# HPLEDShield-v2_5.net
KiCad netlist of a schematic drawn in EAGLE
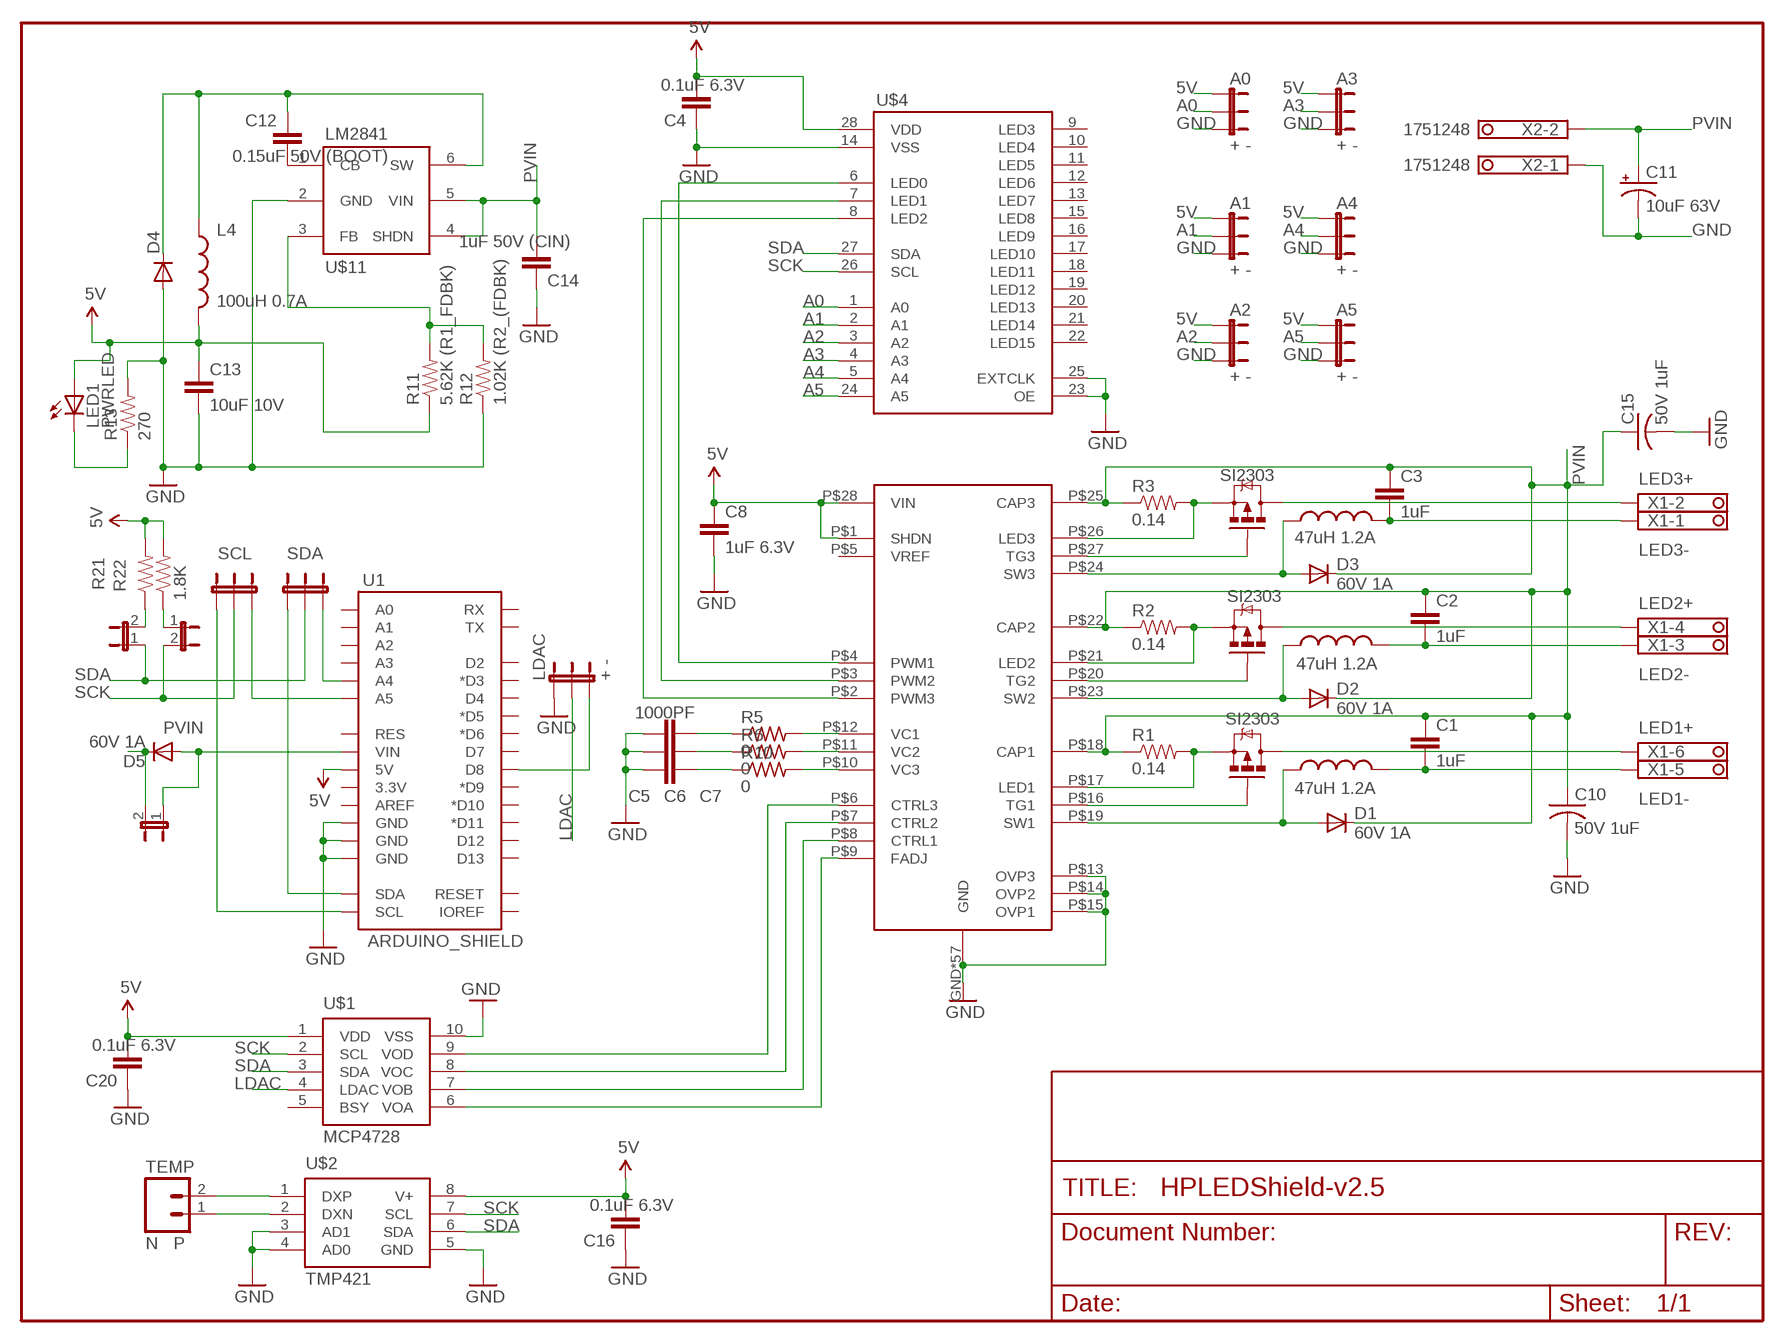
[diagram p0: schematic, sheet 1]

(export (version "E")
  (design (tool "Eeschema 10.0.6"))
  (components
    (comp (ref "A0")
      (value "+ -")
      (footprint "eagle-import:SJ_3")
      (libsource (lib "eagle-import") (part "JUMPER-3SMD"))
    )
    (comp (ref "A1")
      (value "+ -")
      (footprint "eagle-import:SJ_3")
      (libsource (lib "eagle-import") (part "JUMPER-3SMD"))
    )
    (comp (ref "A2")
      (value "+ -")
      (footprint "eagle-import:SJ_3")
      (libsource (lib "eagle-import") (part "JUMPER-3SMD"))
    )
    (comp (ref "A3")
      (value "+ -")
      (footprint "eagle-import:SJ_3")
      (libsource (lib "eagle-import") (part "JUMPER-3SMD"))
    )
    (comp (ref "A4")
      (value "+ -")
      (footprint "eagle-import:SJ_3")
      (libsource (lib "eagle-import") (part "JUMPER-3SMD"))
    )
    (comp (ref "A5")
      (value "+ -")
      (footprint "eagle-import:SJ_3")
      (libsource (lib "eagle-import") (part "JUMPER-3SMD"))
    )
    (comp (ref "C1")
      (value "1uF")
      (footprint "eagle-import:0805")
      (libsource (lib "eagle-import") (part "CAP0805"))
    )
    (comp (ref "C2")
      (value "1uF")
      (footprint "eagle-import:0805")
      (libsource (lib "eagle-import") (part "CAP0805"))
    )
    (comp (ref "C3")
      (value "1uF")
      (footprint "eagle-import:0805")
      (libsource (lib "eagle-import") (part "CAP0805"))
    )
    (comp (ref "C4")
      (value "0.1uF 6.3V")
      (footprint "eagle-import:0402-CAP")
      (libsource (lib "eagle-import") (part "CAP0402-CAP"))
    )
    (comp (ref "C5")
      (value "1000PF")
      (footprint "eagle-import:0402-CAP")
      (libsource (lib "eagle-import") (part "CAP0402-CAP"))
    )
    (comp (ref "C6")
      (value "1000PF")
      (footprint "eagle-import:0402-CAP")
      (libsource (lib "eagle-import") (part "CAP0402-CAP"))
    )
    (comp (ref "C7")
      (value "1000PF")
      (footprint "eagle-import:0402-CAP")
      (libsource (lib "eagle-import") (part "CAP0402-CAP"))
    )
    (comp (ref "C8")
      (value "1uF 6.3V")
      (footprint "eagle-import:0402-CAP")
      (libsource (lib "eagle-import") (part "CAP0402-CAP"))
    )
    (comp (ref "C10")
      (value "50V 1uF")
      (footprint "eagle-import:C1210")
      (libsource (lib "eagle-import") (part "C-USC1210"))
    )
    (comp (ref "C11")
      (value "10uF 63V")
      (footprint "eagle-import:PANASONIC_D")
      (libsource (lib "eagle-import") (part "CAP_POLD"))
    )
    (comp (ref "C12")
      (value "0.15uF 50V (BOOT)")
      (footprint "eagle-import:0603-CAP")
      (libsource (lib "eagle-import") (part "CAP0603-CAP"))
    )
    (comp (ref "C13")
      (value "10uF 10V")
      (footprint "eagle-import:0805")
      (libsource (lib "eagle-import") (part "CAP0805"))
    )
    (comp (ref "C14")
      (value "1uF 50V (CIN)")
      (footprint "eagle-import:1206")
      (libsource (lib "eagle-import") (part "CAP1206"))
    )
    (comp (ref "C15")
      (value "50V 1uF")
      (footprint "eagle-import:C1210")
      (libsource (lib "eagle-import") (part "C-USC1210"))
    )
    (comp (ref "C16")
      (value "0.1uF 6.3V")
      (footprint "eagle-import:0402-CAP")
      (libsource (lib "eagle-import") (part "CAP0402-CAP"))
    )
    (comp (ref "C20")
      (value "0.1uF 6.3V")
      (footprint "eagle-import:0402-CAP")
      (libsource (lib "eagle-import") (part "CAP0402-CAP"))
    )
    (comp (ref "D1")
      (value "60V 1A")
      (footprint "eagle-import:SOD123")
      (libsource (lib "eagle-import") (part "DIODES0D123"))
    )
    (comp (ref "D2")
      (value "60V 1A")
      (footprint "eagle-import:SOD123")
      (libsource (lib "eagle-import") (part "DIODES0D123"))
    )
    (comp (ref "D3")
      (value "60V 1A")
      (footprint "eagle-import:SOD123")
      (libsource (lib "eagle-import") (part "DIODES0D123"))
    )
    (comp (ref "D4")
      (value "DIODE-SCHOTTKY_ 60V 1A")
      (footprint "eagle-import:SOD123")
      (libsource (lib "eagle-import") (part "DIODES0D123"))
    )
    (comp (ref "D5")
      (value "60V 1A")
      (footprint "eagle-import:SOD123")
      (libsource (lib "eagle-import") (part "DIODES0D123"))
    )
    (comp (ref "JP1")
      (value "PWM3")
      (footprint "eagle-import:SJ_2S-NO")
      (libsource (lib "eagle-import") (part "JUMPER-2SMD-NO"))
    )
    (comp (ref "JP2")
      (value "PWM3")
      (footprint "eagle-import:SJ_2S")
      (libsource (lib "eagle-import") (part "JUMPER-2SMD-NC"))
    )
    (comp (ref "JP3")
      (value "PWM3")
      (footprint "eagle-import:SJ_2S")
      (libsource (lib "eagle-import") (part "JUMPER-2SMD-NC"))
    )
    (comp (ref "L1")
      (value "47uH 1.2A")
      (footprint "eagle-import:ELL8TP")
      (libsource (lib "eagle-import") (part "INDUCTORELL8"))
    )
    (comp (ref "L2")
      (value "47uH 1.2A")
      (footprint "eagle-import:ELL8TP")
      (libsource (lib "eagle-import") (part "INDUCTORELL8"))
    )
    (comp (ref "L3")
      (value "47uH 1.2A")
      (footprint "eagle-import:ELL8TP")
      (libsource (lib "eagle-import") (part "INDUCTORELL8"))
    )
    (comp (ref "L4")
      (value "100uH 0.7A")
      (footprint "eagle-import:ELL6UH")
      (libsource (lib "eagle-import") (part "INDUCTOR6UH"))
    )
    (comp (ref "LDAC")
      (value "+ -")
      (footprint "eagle-import:SJ_3")
      (libsource (lib "eagle-import") (part "JUMPER-3SMD"))
    )
    (comp (ref "LED1")
      (value "PWRLED")
      (footprint "eagle-import:LED-0603")
      (libsource (lib "eagle-import") (part "LED0603"))
    )
    (comp (ref "LT3496")
      (value "LT3496")
      (footprint "eagle-import:LT3694_TSSOP")
      (libsource (lib "eagle-import") (part "LT3496"))
    )
    (comp (ref "Q1")
      (value "SI2303")
      (footprint "eagle-import:SOT-23")
      (libsource (lib "eagle-import") (part "SI2303"))
    )
    (comp (ref "Q2")
      (value "SI2303")
      (footprint "eagle-import:SOT-23")
      (libsource (lib "eagle-import") (part "SI2303"))
    )
    (comp (ref "Q3")
      (value "SI2303")
      (footprint "eagle-import:SOT-23")
      (libsource (lib "eagle-import") (part "SI2303"))
    )
    (comp (ref "R1")
      (value "0.14")
      (footprint "eagle-import:0603-RES")
      (libsource (lib "eagle-import") (part "RESISTOR0603-RES"))
    )
    (comp (ref "R2")
      (value "0.14")
      (footprint "eagle-import:0603-RES")
      (libsource (lib "eagle-import") (part "RESISTOR0603-RES"))
    )
    (comp (ref "R3")
      (value "0.14")
      (footprint "eagle-import:0603-RES")
      (libsource (lib "eagle-import") (part "RESISTOR0603-RES"))
    )
    (comp (ref "R5")
      (value "0")
      (footprint "eagle-import:R0402")
      (libsource (lib "eagle-import") (part "R-US_R0402"))
    )
    (comp (ref "R6")
      (value "0")
      (footprint "eagle-import:R0402")
      (libsource (lib "eagle-import") (part "R-US_R0402"))
    )
    (comp (ref "R10")
      (value "0")
      (footprint "eagle-import:R0402")
      (libsource (lib "eagle-import") (part "R-US_R0402"))
    )
    (comp (ref "R11")
      (value "5.62K (R1_FDBK)")
      (footprint "eagle-import:0603-RES")
      (libsource (lib "eagle-import") (part "RESISTOR0603-RES"))
    )
    (comp (ref "R12")
      (value "1.02K (R2_(FDBK)")
      (footprint "eagle-import:0603-RES")
      (libsource (lib "eagle-import") (part "RESISTOR0603-RES"))
    )
    (comp (ref "R13")
      (value "270")
      (footprint "eagle-import:0603-RES")
      (libsource (lib "eagle-import") (part "RESISTOR0603-RES"))
    )
    (comp (ref "R21")
      (value "1.8K")
      (footprint "eagle-import:0402-RES")
      (libsource (lib "eagle-import") (part "RESISTOR0402-RES"))
    )
    (comp (ref "R22")
      (value "1.8K")
      (footprint "eagle-import:0402-RES")
      (libsource (lib "eagle-import") (part "RESISTOR0402-RES"))
    )
    (comp (ref "SCL")
      (value "JUMPER-3SMD")
      (footprint "eagle-import:SJ_3")
      (libsource (lib "eagle-import") (part "JUMPER-3SMD"))
    )
    (comp (ref "SDA")
      (value "JUMPER-3SMD")
      (footprint "eagle-import:SJ_3")
      (libsource (lib "eagle-import") (part "JUMPER-3SMD"))
    )
    (comp (ref "TEMP")
      (value "N P")
      (footprint "eagle-import:1X02")
      (libsource (lib "eagle-import") (part "M02PTH"))
    )
    (comp (ref "U$1")
      (value "MCP4728")
      (footprint "eagle-import:MSOP10")
      (libsource (lib "eagle-import") (part "MCP4728"))
    )
    (comp (ref "U$2")
      (value "TMP421")
      (footprint "eagle-import:SOT23-8")
      (libsource (lib "eagle-import") (part "TMP421"))
    )
    (comp (ref "U$4")
      (value "PCA9685")
      (footprint "eagle-import:TSSOP28")
      (libsource (lib "eagle-import") (part "PCA9685"))
    )
    (comp (ref "U$11")
      (value "LM2841")
      (footprint "eagle-import:TSOT-6")
      (libsource (lib "eagle-import") (part "LM2841"))
    )
    (comp (ref "U1")
      (value "ARDUINO_SHIELD")
      (footprint "eagle-import:DUEMILANOVE_VIAS")
      (libsource (lib "eagle-import") (part "ARDUINO_SHIELDNO_SILK"))
    )
    (comp (ref "X1")
      (value "LED1+")
      (footprint "eagle-import:1751280")
      (fields (field (name "MPN") "1751280"))
      (libsource (lib "eagle-import") (part "1751280"))
    )
    (comp (ref "X2")
      (value "1751248")
      (footprint "eagle-import:1751248")
      (libsource (lib "eagle-import") (part "1751248"))
    )
  )
  (nets
    (net (code "1") (name "/A0") (class "Default")
      (node (ref "A0") (pin "2") (pinfunction "2_2") (pintype "passive"))
      (node (ref "U$4") (pin "1") (pinfunction "A0_1") (pintype "bidirectional"))
    )
    (net (code "2") (name "/A1") (class "Default")
      (node (ref "A1") (pin "2") (pinfunction "2_2") (pintype "passive"))
      (node (ref "U$4") (pin "2") (pinfunction "A1_2") (pintype "bidirectional"))
    )
    (net (code "3") (name "/A2") (class "Default")
      (node (ref "A2") (pin "2") (pinfunction "2_2") (pintype "passive"))
      (node (ref "U$4") (pin "3") (pinfunction "A2_3") (pintype "bidirectional"))
    )
    (net (code "4") (name "/A3") (class "Default")
      (node (ref "A3") (pin "2") (pinfunction "2_2") (pintype "passive"))
      (node (ref "U$4") (pin "4") (pinfunction "A3_4") (pintype "bidirectional"))
    )
    (net (code "5") (name "/A4") (class "Default")
      (node (ref "A4") (pin "2") (pinfunction "2_2") (pintype "passive"))
      (node (ref "U$4") (pin "5") (pinfunction "A4_5") (pintype "bidirectional"))
    )
    (net (code "6") (name "/A5") (class "Default")
      (node (ref "A5") (pin "2") (pinfunction "2_2") (pintype "passive"))
      (node (ref "U$4") (pin "24") (pinfunction "A5_24") (pintype "bidirectional"))
    )
    (net (code "7") (name "/LDAC") (class "Default")
      (node (ref "LDAC") (pin "2") (pinfunction "2_2") (pintype "passive"))
      (node (ref "U$1") (pin "4") (pinfunction "LDAC_4") (pintype "bidirectional"))
    )
    (net (code "8") (name "/PVIN") (class "Default")
      (node (ref "C1") (pin "1") (pinfunction "1_1") (pintype "passive"))
      (node (ref "C10") (pin "1") (pinfunction "1_1") (pintype "passive"))
      (node (ref "C11") (pin "+") (pinfunction "+_+") (pintype "passive"))
      (node (ref "C14") (pin "2") (pinfunction "2_2") (pintype "passive"))
      (node (ref "C15") (pin "1") (pinfunction "1_1") (pintype "passive"))
      (node (ref "C2") (pin "1") (pinfunction "1_1") (pintype "passive"))
      (node (ref "C3") (pin "1") (pinfunction "1_1") (pintype "passive"))
      (node (ref "D1") (pin "1") (pinfunction "C_1") (pintype "passive"))
      (node (ref "D2") (pin "1") (pinfunction "C_1") (pintype "passive"))
      (node (ref "D3") (pin "1") (pinfunction "C_1") (pintype "passive"))
      (node (ref "D5") (pin "1") (pinfunction "C_1") (pintype "passive"))
      (node (ref "JP1") (pin "2") (pinfunction "2_2") (pintype "passive"))
      (node (ref "LT3496") (pin "P$18") (pinfunction "CAP1_P$18") (pintype "bidirectional"))
      (node (ref "LT3496") (pin "P$22") (pinfunction "CAP2_P$22") (pintype "bidirectional"))
      (node (ref "LT3496") (pin "P$25") (pinfunction "CAP3_P$25") (pintype "bidirectional"))
      (node (ref "R1") (pin "1") (pinfunction "1_1") (pintype "passive"))
      (node (ref "R2") (pin "1") (pinfunction "1_1") (pintype "passive"))
      (node (ref "R3") (pin "1") (pinfunction "1_1") (pintype "passive"))
      (node (ref "U$11") (pin "4") (pinfunction "SHDN_4") (pintype "bidirectional"))
      (node (ref "U$11") (pin "5") (pinfunction "VIN_5") (pintype "bidirectional"))
      (node (ref "X2") (pin "2") (pinfunction "K_2") (pintype "passive"))
    )
    (net (code "9") (name "/SCK") (class "Default")
      (node (ref "JP3") (pin "2") (pinfunction "2_2") (pintype "passive"))
      (node (ref "SCL") (pin "2") (pinfunction "2_2") (pintype "passive"))
      (node (ref "U$1") (pin "2") (pinfunction "SCL_2") (pintype "bidirectional"))
      (node (ref "U$2") (pin "7") (pinfunction "SCL_7") (pintype "bidirectional"))
      (node (ref "U$4") (pin "26") (pinfunction "SCL_26") (pintype "bidirectional"))
    )
    (net (code "10") (name "/SDA") (class "Default")
      (node (ref "JP2") (pin "1") (pinfunction "1_1") (pintype "passive"))
      (node (ref "SDA") (pin "2") (pinfunction "2_2") (pintype "passive"))
      (node (ref "U$1") (pin "3") (pinfunction "SDA_3") (pintype "bidirectional"))
      (node (ref "U$2") (pin "6") (pinfunction "SDA_6") (pintype "bidirectional"))
      (node (ref "U$4") (pin "27") (pinfunction "SDA_27") (pintype "bidirectional"))
    )
    (net (code "11") (name "5V") (class "Default")
      (node (ref "A0") (pin "1") (pinfunction "1_1") (pintype "passive"))
      (node (ref "A1") (pin "1") (pinfunction "1_1") (pintype "passive"))
      (node (ref "A2") (pin "1") (pinfunction "1_1") (pintype "passive"))
      (node (ref "A3") (pin "1") (pinfunction "1_1") (pintype "passive"))
      (node (ref "A4") (pin "1") (pinfunction "1_1") (pintype "passive"))
      (node (ref "A5") (pin "1") (pinfunction "1_1") (pintype "passive"))
      (node (ref "C13") (pin "1") (pinfunction "1_1") (pintype "passive"))
      (node (ref "C16") (pin "2") (pinfunction "2_2") (pintype "passive"))
      (node (ref "C20") (pin "2") (pinfunction "2_2") (pintype "passive"))
      (node (ref "C4") (pin "2") (pinfunction "2_2") (pintype "passive"))
      (node (ref "C8") (pin "1") (pinfunction "1_1") (pintype "passive"))
      (node (ref "L4") (pin "P$2") (pinfunction "2_P$2") (pintype "passive"))
      (node (ref "LED1") (pin "A") (pinfunction "A_A") (pintype "passive"))
      (node (ref "LT3496") (pin "P$1") (pinfunction "SHDN_P$1") (pintype "bidirectional"))
      (node (ref "LT3496") (pin "P$28") (pinfunction "VIN_P$28") (pintype "power_in"))
      (node (ref "R11") (pin "1") (pinfunction "1_1") (pintype "passive"))
      (node (ref "R21") (pin "2") (pinfunction "2_2") (pintype "passive"))
      (node (ref "R22") (pin "2") (pinfunction "2_2") (pintype "passive"))
      (node (ref "U$1") (pin "1") (pinfunction "VDD_1") (pintype "bidirectional"))
      (node (ref "U$2") (pin "8") (pinfunction "V+_8") (pintype "bidirectional"))
      (node (ref "U$4") (pin "28") (pinfunction "VDD_28") (pintype "bidirectional"))
      (node (ref "U1") (pin "5V") (pinfunction "5V_5V") (pintype "bidirectional"))
    )
    (net (code "12") (name "GND") (class "Default")
      (node (ref "A0") (pin "3") (pinfunction "3_3") (pintype "passive"))
      (node (ref "A1") (pin "3") (pinfunction "3_3") (pintype "passive"))
      (node (ref "A2") (pin "3") (pinfunction "3_3") (pintype "passive"))
      (node (ref "A3") (pin "3") (pinfunction "3_3") (pintype "passive"))
      (node (ref "A4") (pin "3") (pinfunction "3_3") (pintype "passive"))
      (node (ref "A5") (pin "3") (pinfunction "3_3") (pintype "passive"))
      (node (ref "C10") (pin "2") (pinfunction "2_2") (pintype "passive"))
      (node (ref "C11") (pin "-") (pinfunction "-_-") (pintype "passive"))
      (node (ref "C13") (pin "2") (pinfunction "2_2") (pintype "passive"))
      (node (ref "C14") (pin "1") (pinfunction "1_1") (pintype "passive"))
      (node (ref "C15") (pin "2") (pinfunction "2_2") (pintype "passive"))
      (node (ref "C16") (pin "1") (pinfunction "1_1") (pintype "passive"))
      (node (ref "C20") (pin "1") (pinfunction "1_1") (pintype "passive"))
      (node (ref "C4") (pin "1") (pinfunction "1_1") (pintype "passive"))
      (node (ref "C5") (pin "1") (pinfunction "1_1") (pintype "passive"))
      (node (ref "C6") (pin "1") (pinfunction "1_1") (pintype "passive"))
      (node (ref "C7") (pin "1") (pinfunction "1_1") (pintype "passive"))
      (node (ref "C8") (pin "2") (pinfunction "2_2") (pintype "passive"))
      (node (ref "D4") (pin "2") (pinfunction "A_2") (pintype "passive"))
      (node (ref "LDAC") (pin "1") (pinfunction "1_1") (pintype "passive"))
      (node (ref "LT3496") (pin "GND") (pinfunction "GND_GND") (pintype "bidirectional"))
      (node (ref "LT3496") (pin "P$13") (pinfunction "OVP3_P$13") (pintype "bidirectional"))
      (node (ref "LT3496") (pin "P$14") (pinfunction "OVP2_P$14") (pintype "bidirectional"))
      (node (ref "LT3496") (pin "P$15") (pinfunction "OVP1_P$15") (pintype "bidirectional"))
      (node (ref "LT3496") (pin "P$29") (pinfunction "GND_P$29") (pintype "bidirectional"))
      (node (ref "LT3496") (pin "P$30") (pinfunction "GND_P$30") (pintype "bidirectional"))
      (node (ref "LT3496") (pin "P$31") (pinfunction "GND_P$31") (pintype "bidirectional"))
      (node (ref "LT3496") (pin "P$32") (pinfunction "GND_P$32") (pintype "bidirectional"))
      (node (ref "LT3496") (pin "P$33") (pinfunction "GND_P$33") (pintype "bidirectional"))
      (node (ref "LT3496") (pin "P$34") (pinfunction "GND_P$34") (pintype "bidirectional"))
      (node (ref "LT3496") (pin "P$35") (pinfunction "GND_P$35") (pintype "bidirectional"))
      (node (ref "LT3496") (pin "P$36") (pinfunction "GND_P$36") (pintype "bidirectional"))
      (node (ref "LT3496") (pin "P$37") (pinfunction "GND_P$37") (pintype "bidirectional"))
      (node (ref "LT3496") (pin "P$38") (pinfunction "GND_P$38") (pintype "bidirectional"))
      (node (ref "LT3496") (pin "P$39") (pinfunction "GND_P$39") (pintype "bidirectional"))
      (node (ref "LT3496") (pin "P$40") (pinfunction "GND_P$40") (pintype "bidirectional"))
      (node (ref "LT3496") (pin "P$41") (pinfunction "GND_P$41") (pintype "bidirectional"))
      (node (ref "LT3496") (pin "P$42") (pinfunction "GND_P$42") (pintype "bidirectional"))
      (node (ref "LT3496") (pin "P$43") (pinfunction "GND_P$43") (pintype "bidirectional"))
      (node (ref "LT3496") (pin "P$44") (pinfunction "GND_P$44") (pintype "bidirectional"))
      (node (ref "LT3496") (pin "P$45") (pinfunction "GND_P$45") (pintype "bidirectional"))
      (node (ref "LT3496") (pin "P$46") (pinfunction "GND_P$46") (pintype "bidirectional"))
      (node (ref "LT3496") (pin "P$47") (pinfunction "GND_P$47") (pintype "bidirectional"))
      (node (ref "LT3496") (pin "P$48") (pinfunction "GND_P$48") (pintype "bidirectional"))
      (node (ref "LT3496") (pin "P$49") (pinfunction "GND_P$49") (pintype "bidirectional"))
      (node (ref "LT3496") (pin "P$50") (pinfunction "GND_P$50") (pintype "bidirectional"))
      (node (ref "LT3496") (pin "P$51") (pinfunction "GND_P$51") (pintype "bidirectional"))
      (node (ref "LT3496") (pin "P$52") (pinfunction "GND_P$52") (pintype "bidirectional"))
      (node (ref "LT3496") (pin "P$53") (pinfunction "GND_P$53") (pintype "bidirectional"))
      (node (ref "LT3496") (pin "P$54") (pinfunction "GND_P$54") (pintype "bidirectional"))
      (node (ref "LT3496") (pin "P$55") (pinfunction "GND_P$55") (pintype "bidirectional"))
      (node (ref "LT3496") (pin "P$56") (pinfunction "GND_P$56") (pintype "bidirectional"))
      (node (ref "LT3496") (pin "P$57") (pinfunction "GND_P$57") (pintype "bidirectional"))
      (node (ref "LT3496") (pin "P$58") (pinfunction "GND_P$58") (pintype "bidirectional"))
      (node (ref "LT3496") (pin "P$59") (pinfunction "GND_P$59") (pintype "bidirectional"))
      (node (ref "LT3496") (pin "P$60") (pinfunction "GND_P$60") (pintype "bidirectional"))
      (node (ref "LT3496") (pin "P$61") (pinfunction "GND_P$61") (pintype "bidirectional"))
      (node (ref "LT3496") (pin "P$62") (pinfunction "GND_P$62") (pintype "bidirectional"))
      (node (ref "LT3496") (pin "P$63") (pinfunction "GND_P$63") (pintype "bidirectional"))
      (node (ref "LT3496") (pin "P$64") (pinfunction "GND_P$64") (pintype "bidirectional"))
      (node (ref "LT3496") (pin "P$65") (pinfunction "GND_P$65") (pintype "bidirectional"))
      (node (ref "LT3496") (pin "P$66") (pinfunction "GND_P$66") (pintype "bidirectional"))
      (node (ref "LT3496") (pin "P$67") (pinfunction "GND_P$67") (pintype "bidirectional"))
      (node (ref "LT3496") (pin "P$68") (pinfunction "GND_P$68") (pintype "bidirectional"))
      (node (ref "LT3496") (pin "P$69") (pinfunction "GND_P$69") (pintype "bidirectional"))
      (node (ref "LT3496") (pin "P$70") (pinfunction "GND_P$70") (pintype "bidirectional"))
      (node (ref "LT3496") (pin "P$71") (pinfunction "GND_P$71") (pintype "bidirectional"))
      (node (ref "LT3496") (pin "P$72") (pinfunction "GND_P$72") (pintype "bidirectional"))
      (node (ref "LT3496") (pin "P$73") (pinfunction "GND_P$73") (pintype "bidirectional"))
      (node (ref "LT3496") (pin "P$74") (pinfunction "GND_P$74") (pintype "bidirectional"))
      (node (ref "LT3496") (pin "P$75") (pinfunction "GND_P$75") (pintype "bidirectional"))
      (node (ref "LT3496") (pin "P$76") (pinfunction "GND_P$76") (pintype "bidirectional"))
      (node (ref "LT3496") (pin "P$77") (pinfunction "GND_P$77") (pintype "bidirectional"))
      (node (ref "LT3496") (pin "P$78") (pinfunction "GND_P$78") (pintype "bidirectional"))
      (node (ref "LT3496") (pin "P$79") (pinfunction "GND_P$79") (pintype "bidirectional"))
      (node (ref "LT3496") (pin "P$80") (pinfunction "GND_P$80") (pintype "bidirectional"))
      (node (ref "LT3496") (pin "P$81") (pinfunction "GND_P$81") (pintype "bidirectional"))
      (node (ref "LT3496") (pin "P$82") (pinfunction "GND_P$82") (pintype "bidirectional"))
      (node (ref "LT3496") (pin "P$83") (pinfunction "GND_P$83") (pintype "bidirectional"))
      (node (ref "LT3496") (pin "P$84") (pinfunction "GND_P$84") (pintype "bidirectional"))
      (node (ref "R12") (pin "1") (pinfunction "1_1") (pintype "passive"))
      (node (ref "R13") (pin "2") (pinfunction "2_2") (pintype "passive"))
      (node (ref "U$1") (pin "10") (pinfunction "VSS_10") (pintype "bidirectional"))
      (node (ref "U$11") (pin "2") (pinfunction "GND_2") (pintype "bidirectional"))
      (node (ref "U$2") (pin "3") (pinfunction "AD1_3") (pintype "bidirectional"))
      (node (ref "U$2") (pin "4") (pinfunction "AD0_4") (pintype "bidirectional"))
      (node (ref "U$2") (pin "5") (pinfunction "GND_5") (pintype "bidirectional"))
      (node (ref "U$4") (pin "14") (pinfunction "VSS_14") (pintype "bidirectional"))
      (node (ref "U$4") (pin "23") (pinfunction "OE_23") (pintype "bidirectional"))
      (node (ref "U$4") (pin "25") (pinfunction "EXTCLK_25") (pintype "bidirectional"))
      (node (ref "U1") (pin "GND@0") (pinfunction "GND_GND@0") (pintype "bidirectional"))
      (node (ref "U1") (pin "GND@1") (pinfunction "GND_GND@1") (pintype "bidirectional"))
      (node (ref "U1") (pin "GND@2") (pinfunction "GND_GND@2") (pintype "bidirectional"))
      (node (ref "X2") (pin "1") (pinfunction "K_1") (pintype "passive"))
    )
    (net (code "13") (name "Net-(C5-Pad2)") (class "Default")
      (node (ref "C5") (pin "2") (pinfunction "2_2") (pintype "passive"))
      (node (ref "R10") (pin "1") (pinfunction "1_1") (pintype "passive"))
    )
    (net (code "14") (name "Net-(C6-Pad2)") (class "Default")
      (node (ref "C6") (pin "2") (pinfunction "2_2") (pintype "passive"))
      (node (ref "R6") (pin "1") (pinfunction "1_1") (pintype "passive"))
    )
    (net (code "15") (name "Net-(C7-Pad2)") (class "Default")
      (node (ref "C7") (pin "2") (pinfunction "2_2") (pintype "passive"))
      (node (ref "R5") (pin "1") (pinfunction "1_1") (pintype "passive"))
    )
    (net (code "16") (name "Net-(D1-A)") (class "Default")
      (node (ref "D1") (pin "2") (pinfunction "A_2") (pintype "passive"))
      (node (ref "L1") (pin "P$1") (pinfunction "1_P$1") (pintype "passive"))
      (node (ref "LT3496") (pin "P$19") (pinfunction "SW1_P$19") (pintype "bidirectional"))
    )
    (net (code "17") (name "Net-(D2-A)") (class "Default")
      (node (ref "D2") (pin "2") (pinfunction "A_2") (pintype "passive"))
      (node (ref "L2") (pin "P$1") (pinfunction "1_P$1") (pintype "passive"))
      (node (ref "LT3496") (pin "P$23") (pinfunction "SW2_P$23") (pintype "bidirectional"))
    )
    (net (code "18") (name "Net-(D3-A)") (class "Default")
      (node (ref "D3") (pin "2") (pinfunction "A_2") (pintype "passive"))
      (node (ref "L3") (pin "P$1") (pinfunction "1_P$1") (pintype "passive"))
      (node (ref "LT3496") (pin "P$24") (pinfunction "SW3_P$24") (pintype "bidirectional"))
    )
    (net (code "19") (name "Net-(D4-C)") (class "Default")
      (node (ref "C12") (pin "1") (pinfunction "1_1") (pintype "passive"))
      (node (ref "D4") (pin "1") (pinfunction "C_1") (pintype "passive"))
      (node (ref "L4") (pin "P$1") (pinfunction "1_P$1") (pintype "passive"))
      (node (ref "U$11") (pin "6") (pinfunction "SW_6") (pintype "bidirectional"))
    )
    (net (code "20") (name "Net-(D5-A)") (class "Default")
      (node (ref "D5") (pin "2") (pinfunction "A_2") (pintype "passive"))
      (node (ref "JP1") (pin "1") (pinfunction "1_1") (pintype "passive"))
      (node (ref "U1") (pin "VIN") (pinfunction "VIN_VIN") (pintype "bidirectional"))
    )
    (net (code "21") (name "Net-(JP2-Pad2)") (class "Default")
      (node (ref "JP2") (pin "2") (pinfunction "2_2") (pintype "passive"))
      (node (ref "R21") (pin "1") (pinfunction "1_1") (pintype "passive"))
    )
    (net (code "22") (name "Net-(JP3-Pad1)") (class "Default")
      (node (ref "JP3") (pin "1") (pinfunction "1_1") (pintype "passive"))
      (node (ref "R22") (pin "1") (pinfunction "1_1") (pintype "passive"))
    )
    (net (code "23") (name "Net-(L1-2)") (class "Default")
      (node (ref "C1") (pin "2") (pinfunction "2_2") (pintype "passive"))
      (node (ref "L1") (pin "P$2") (pinfunction "2_P$2") (pintype "passive"))
      (node (ref "X1") (pin "5") (pinfunction "K_5") (pintype "passive"))
    )
    (net (code "24") (name "Net-(L2-2)") (class "Default")
      (node (ref "C2") (pin "2") (pinfunction "2_2") (pintype "passive"))
      (node (ref "L2") (pin "P$2") (pinfunction "2_P$2") (pintype "passive"))
      (node (ref "X1") (pin "3") (pinfunction "K_3") (pintype "passive"))
    )
    (net (code "25") (name "Net-(L3-2)") (class "Default")
      (node (ref "C3") (pin "2") (pinfunction "2_2") (pintype "passive"))
      (node (ref "L3") (pin "P$2") (pinfunction "2_P$2") (pintype "passive"))
      (node (ref "X1") (pin "1") (pinfunction "K_1") (pintype "passive"))
    )
    (net (code "26") (name "Net-(LDAC-Pad3)") (class "Default")
      (node (ref "LDAC") (pin "3") (pinfunction "3_3") (pintype "passive"))
      (node (ref "U1") (pin "D8") (pinfunction "D8_D8") (pintype "bidirectional"))
    )
    (net (code "27") (name "Net-(LED1-PadC)") (class "Default")
      (node (ref "LED1") (pin "C") (pinfunction "C_C") (pintype "passive"))
      (node (ref "R13") (pin "1") (pinfunction "1_1") (pintype "passive"))
    )
    (net (code "28") (name "Net-(LT3496-CTRL1)") (class "Default")
      (node (ref "LT3496") (pin "P$8") (pinfunction "CTRL1_P$8") (pintype "bidirectional"))
      (node (ref "U$1") (pin "7") (pinfunction "VOB_7") (pintype "bidirectional"))
    )
    (net (code "29") (name "Net-(LT3496-CTRL2)") (class "Default")
      (node (ref "LT3496") (pin "P$7") (pinfunction "CTRL2_P$7") (pintype "bidirectional"))
      (node (ref "U$1") (pin "8") (pinfunction "VOC_8") (pintype "bidirectional"))
    )
    (net (code "30") (name "Net-(LT3496-CTRL3)") (class "Default")
      (node (ref "LT3496") (pin "P$6") (pinfunction "CTRL3_P$6") (pintype "bidirectional"))
      (node (ref "U$1") (pin "9") (pinfunction "VOD_9") (pintype "bidirectional"))
    )
    (net (code "31") (name "Net-(LT3496-FADJ)") (class "Default")
      (node (ref "LT3496") (pin "P$9") (pinfunction "FADJ_P$9") (pintype "bidirectional"))
      (node (ref "U$1") (pin "6") (pinfunction "VOA_6") (pintype "bidirectional"))
    )
    (net (code "32") (name "Net-(LT3496-LED1)") (class "Default")
      (node (ref "LT3496") (pin "P$17") (pinfunction "LED1_P$17") (pintype "bidirectional"))
      (node (ref "Q1") (pin "2") (pinfunction "S_2") (pintype "passive"))
      (node (ref "R1") (pin "2") (pinfunction "2_2") (pintype "passive"))
    )
    (net (code "33") (name "Net-(LT3496-LED2)") (class "Default")
      (node (ref "LT3496") (pin "P$21") (pinfunction "LED2_P$21") (pintype "bidirectional"))
      (node (ref "Q2") (pin "2") (pinfunction "S_2") (pintype "passive"))
      (node (ref "R2") (pin "2") (pinfunction "2_2") (pintype "passive"))
    )
    (net (code "34") (name "Net-(LT3496-LED3)") (class "Default")
      (node (ref "LT3496") (pin "P$26") (pinfunction "LED3_P$26") (pintype "bidirectional"))
      (node (ref "Q3") (pin "2") (pinfunction "S_2") (pintype "passive"))
      (node (ref "R3") (pin "2") (pinfunction "2_2") (pintype "passive"))
    )
    (net (code "35") (name "Net-(LT3496-PWM1)") (class "Default")
      (node (ref "LT3496") (pin "P$4") (pinfunction "PWM1_P$4") (pintype "bidirectional"))
      (node (ref "U$4") (pin "6") (pinfunction "LED0_6") (pintype "bidirectional"))
    )
    (net (code "36") (name "Net-(LT3496-PWM2)") (class "Default")
      (node (ref "LT3496") (pin "P$3") (pinfunction "PWM2_P$3") (pintype "bidirectional"))
      (node (ref "U$4") (pin "7") (pinfunction "LED1_7") (pintype "bidirectional"))
    )
    (net (code "37") (name "Net-(LT3496-PWM3)") (class "Default")
      (node (ref "LT3496") (pin "P$2") (pinfunction "PWM3_P$2") (pintype "bidirectional"))
      (node (ref "U$4") (pin "8") (pinfunction "LED2_8") (pintype "bidirectional"))
    )
    (net (code "38") (name "Net-(LT3496-TG1)") (class "Default")
      (node (ref "LT3496") (pin "P$16") (pinfunction "TG1_P$16") (pintype "bidirectional"))
      (node (ref "Q1") (pin "1") (pinfunction "G_1") (pintype "passive"))
    )
    (net (code "39") (name "Net-(LT3496-TG2)") (class "Default")
      (node (ref "LT3496") (pin "P$20") (pinfunction "TG2_P$20") (pintype "bidirectional"))
      (node (ref "Q2") (pin "1") (pinfunction "G_1") (pintype "passive"))
    )
    (net (code "40") (name "Net-(LT3496-TG3)") (class "Default")
      (node (ref "LT3496") (pin "P$27") (pinfunction "TG3_P$27") (pintype "bidirectional"))
      (node (ref "Q3") (pin "1") (pinfunction "G_1") (pintype "passive"))
    )
    (net (code "41") (name "Net-(LT3496-VC1)") (class "Default")
      (node (ref "LT3496") (pin "P$12") (pinfunction "VC1_P$12") (pintype "bidirectional"))
      (node (ref "R5") (pin "2") (pinfunction "2_2") (pintype "passive"))
    )
    (net (code "42") (name "Net-(LT3496-VC2)") (class "Default")
      (node (ref "LT3496") (pin "P$11") (pinfunction "VC2_P$11") (pintype "bidirectional"))
      (node (ref "R6") (pin "2") (pinfunction "2_2") (pintype "passive"))
    )
    (net (code "43") (name "Net-(LT3496-VC3)") (class "Default")
      (node (ref "LT3496") (pin "P$10") (pinfunction "VC3_P$10") (pintype "bidirectional"))
      (node (ref "R10") (pin "2") (pinfunction "2_2") (pintype "passive"))
    )
    (net (code "44") (name "Net-(Q1-D)") (class "Default")
      (node (ref "Q1") (pin "3") (pinfunction "D_3") (pintype "passive"))
      (node (ref "X1") (pin "6") (pinfunction "K_6") (pintype "passive"))
    )
    (net (code "45") (name "Net-(Q2-D)") (class "Default")
      (node (ref "Q2") (pin "3") (pinfunction "D_3") (pintype "passive"))
      (node (ref "X1") (pin "4") (pinfunction "K_4") (pintype "passive"))
    )
    (net (code "46") (name "Net-(Q3-D)") (class "Default")
      (node (ref "Q3") (pin "3") (pinfunction "D_3") (pintype "passive"))
      (node (ref "X1") (pin "2") (pinfunction "K_2") (pintype "passive"))
    )
    (net (code "47") (name "Net-(SCL-Pad1)") (class "Default")
      (node (ref "SCL") (pin "1") (pinfunction "1_1") (pintype "passive"))
      (node (ref "U1") (pin "SCL") (pinfunction "SCL_SCL") (pintype "bidirectional"))
    )
    (net (code "48") (name "Net-(SCL-Pad3)") (class "Default")
      (node (ref "SCL") (pin "3") (pinfunction "3_3") (pintype "passive"))
      (node (ref "U1") (pin "A5") (pinfunction "A5_A5") (pintype "bidirectional"))
    )
    (net (code "49") (name "Net-(SDA-Pad1)") (class "Default")
      (node (ref "SDA") (pin "1") (pinfunction "1_1") (pintype "passive"))
      (node (ref "U1") (pin "SDA") (pinfunction "SDA_SDA") (pintype "bidirectional"))
    )
    (net (code "50") (name "Net-(SDA-Pad3)") (class "Default")
      (node (ref "SDA") (pin "3") (pinfunction "3_3") (pintype "passive"))
      (node (ref "U1") (pin "A4") (pinfunction "A4_A4") (pintype "bidirectional"))
    )
    (net (code "51") (name "Net-(U$2-DXN)") (class "Default")
      (node (ref "TEMP") (pin "1") (pinfunction "1_1") (pintype "passive"))
      (node (ref "U$2") (pin "2") (pinfunction "DXN_2") (pintype "bidirectional"))
    )
    (net (code "52") (name "Net-(U$2-DXP)") (class "Default")
      (node (ref "TEMP") (pin "2") (pinfunction "2_2") (pintype "passive"))
      (node (ref "U$2") (pin "1") (pinfunction "DXP_1") (pintype "bidirectional"))
    )
    (net (code "53") (name "Net-(U$11-CB)") (class "Default")
      (node (ref "C12") (pin "2") (pinfunction "2_2") (pintype "passive"))
      (node (ref "U$11") (pin "1") (pinfunction "CB_1") (pintype "bidirectional"))
    )
    (net (code "54") (name "Net-(U$11-FB)") (class "Default")
      (node (ref "R11") (pin "2") (pinfunction "2_2") (pintype "passive"))
      (node (ref "R12") (pin "2") (pinfunction "2_2") (pintype "passive"))
      (node (ref "U$11") (pin "3") (pinfunction "FB_3") (pintype "bidirectional"))
    )
    (net (code "55") (name "unconnected-(LT3496-VREF-PadP$5)") (class "Default")
      (node (ref "LT3496") (pin "P$5") (pinfunction "VREF_P$5") (pintype "bidirectional"))
    )
    (net (code "56") (name "unconnected-(U$1-BSY-Pad5)") (class "Default")
      (node (ref "U$1") (pin "5") (pinfunction "BSY_5") (pintype "bidirectional"))
    )
    (net (code "57") (name "unconnected-(U$4-LED3-Pad9)") (class "Default")
      (node (ref "U$4") (pin "9") (pinfunction "LED3_9") (pintype "bidirectional"))
    )
    (net (code "58") (name "unconnected-(U$4-LED4-Pad10)") (class "Default")
      (node (ref "U$4") (pin "10") (pinfunction "LED4_10") (pintype "bidirectional"))
    )
    (net (code "59") (name "unconnected-(U$4-LED5-Pad11)") (class "Default")
      (node (ref "U$4") (pin "11") (pinfunction "LED5_11") (pintype "bidirectional"))
    )
    (net (code "60") (name "unconnected-(U$4-LED6-Pad12)") (class "Default")
      (node (ref "U$4") (pin "12") (pinfunction "LED6_12") (pintype "bidirectional"))
    )
    (net (code "61") (name "unconnected-(U$4-LED7-Pad13)") (class "Default")
      (node (ref "U$4") (pin "13") (pinfunction "LED7_13") (pintype "bidirectional"))
    )
    (net (code "62") (name "unconnected-(U$4-LED8-Pad15)") (class "Default")
      (node (ref "U$4") (pin "15") (pinfunction "LED8_15") (pintype "bidirectional"))
    )
    (net (code "63") (name "unconnected-(U$4-LED9-Pad16)") (class "Default")
      (node (ref "U$4") (pin "16") (pinfunction "LED9_16") (pintype "bidirectional"))
    )
    (net (code "64") (name "unconnected-(U$4-LED10-Pad17)") (class "Default")
      (node (ref "U$4") (pin "17") (pinfunction "LED10_17") (pintype "bidirectional"))
    )
    (net (code "65") (name "unconnected-(U$4-LED11-Pad18)") (class "Default")
      (node (ref "U$4") (pin "18") (pinfunction "LED11_18") (pintype "bidirectional"))
    )
    (net (code "66") (name "unconnected-(U$4-LED12-Pad19)") (class "Default")
      (node (ref "U$4") (pin "19") (pinfunction "LED12_19") (pintype "bidirectional"))
    )
    (net (code "67") (name "unconnected-(U$4-LED13-Pad20)") (class "Default")
      (node (ref "U$4") (pin "20") (pinfunction "LED13_20") (pintype "bidirectional"))
    )
    (net (code "68") (name "unconnected-(U$4-LED14-Pad21)") (class "Default")
      (node (ref "U$4") (pin "21") (pinfunction "LED14_21") (pintype "bidirectional"))
    )
    (net (code "69") (name "unconnected-(U$4-LED15-Pad22)") (class "Default")
      (node (ref "U$4") (pin "22") (pinfunction "LED15_22") (pintype "bidirectional"))
    )
    (net (code "70") (name "unconnected-(U1-*D3-PadD3)") (class "Default")
      (node (ref "U1") (pin "D3") (pinfunction "*D3_D3") (pintype "bidirectional"))
    )
    (net (code "71") (name "unconnected-(U1-*D5-PadD5)") (class "Default")
      (node (ref "U1") (pin "D5") (pinfunction "*D5_D5") (pintype "bidirectional"))
    )
    (net (code "72") (name "unconnected-(U1-*D6-PadD6)") (class "Default")
      (node (ref "U1") (pin "D6") (pinfunction "*D6_D6") (pintype "bidirectional"))
    )
    (net (code "73") (name "unconnected-(U1-*D9-PadD9)") (class "Default")
      (node (ref "U1") (pin "D9") (pinfunction "*D9_D9") (pintype "bidirectional"))
    )
    (net (code "74") (name "unconnected-(U1-*D10-PadD10)") (class "Default")
      (node (ref "U1") (pin "D10") (pinfunction "*D10_D10") (pintype "bidirectional"))
    )
    (net (code "75") (name "unconnected-(U1-*D11-PadD11)") (class "Default")
      (node (ref "U1") (pin "D11") (pinfunction "*D11_D11") (pintype "bidirectional"))
    )
    (net (code "76") (name "unconnected-(U1-Pad3.3V)") (class "Default")
      (node (ref "U1") (pin "3.3V") (pinfunction "3.3V_3.3V") (pintype "bidirectional"))
    )
    (net (code "77") (name "unconnected-(U1-PadA0)") (class "Default")
      (node (ref "U1") (pin "A0") (pinfunction "A0_A0") (pintype "bidirectional"))
    )
    (net (code "78") (name "unconnected-(U1-PadA1)") (class "Default")
      (node (ref "U1") (pin "A1") (pinfunction "A1_A1") (pintype "bidirectional"))
    )
    (net (code "79") (name "unconnected-(U1-PadA2)") (class "Default")
      (node (ref "U1") (pin "A2") (pinfunction "A2_A2") (pintype "bidirectional"))
    )
    (net (code "80") (name "unconnected-(U1-PadA3)") (class "Default")
      (node (ref "U1") (pin "A3") (pinfunction "A3_A3") (pintype "bidirectional"))
    )
    (net (code "81") (name "unconnected-(U1-PadAREF)") (class "Default")
      (node (ref "U1") (pin "AREF") (pinfunction "AREF_AREF") (pintype "bidirectional"))
    )
    (net (code "82") (name "unconnected-(U1-PadD2)") (class "Default")
      (node (ref "U1") (pin "D2") (pinfunction "D2_D2") (pintype "bidirectional"))
    )
    (net (code "83") (name "unconnected-(U1-PadD4)") (class "Default")
      (node (ref "U1") (pin "D4") (pinfunction "D4_D4") (pintype "bidirectional"))
    )
    (net (code "84") (name "unconnected-(U1-PadD7)") (class "Default")
      (node (ref "U1") (pin "D7") (pinfunction "D7_D7") (pintype "bidirectional"))
    )
    (net (code "85") (name "unconnected-(U1-PadD12)") (class "Default")
      (node (ref "U1") (pin "D12") (pinfunction "D12_D12") (pintype "bidirectional"))
    )
    (net (code "86") (name "unconnected-(U1-PadD13)") (class "Default")
      (node (ref "U1") (pin "D13") (pinfunction "D13_D13") (pintype "bidirectional"))
    )
    (net (code "87") (name "unconnected-(U1-PadIOREF)") (class "Default")
      (node (ref "U1") (pin "IOREF") (pinfunction "IOREF_IOREF") (pintype "bidirectional"))
    )
    (net (code "88") (name "unconnected-(U1-PadRX)") (class "Default")
      (node (ref "U1") (pin "RX") (pinfunction "RX_RX") (pintype "bidirectional"))
    )
    (net (code "89") (name "unconnected-(U1-PadTX)") (class "Default")
      (node (ref "U1") (pin "TX") (pinfunction "TX_TX") (pintype "bidirectional"))
    )
    (net (code "90") (name "unconnected-(U1-RES-PadRESET)") (class "Default")
      (node (ref "U1") (pin "RESET") (pinfunction "RES_RESET") (pintype "bidirectional"))
    )
    (net (code "91") (name "unconnected-(U1-RESET-PadRES$1)") (class "Default")
      (node (ref "U1") (pin "RES$1") (pinfunction "RESET_RES$1") (pintype "bidirectional"))
    )
  )
)
